# main-uass.net
KiCad netlist of a schematic drawn in EAGLE
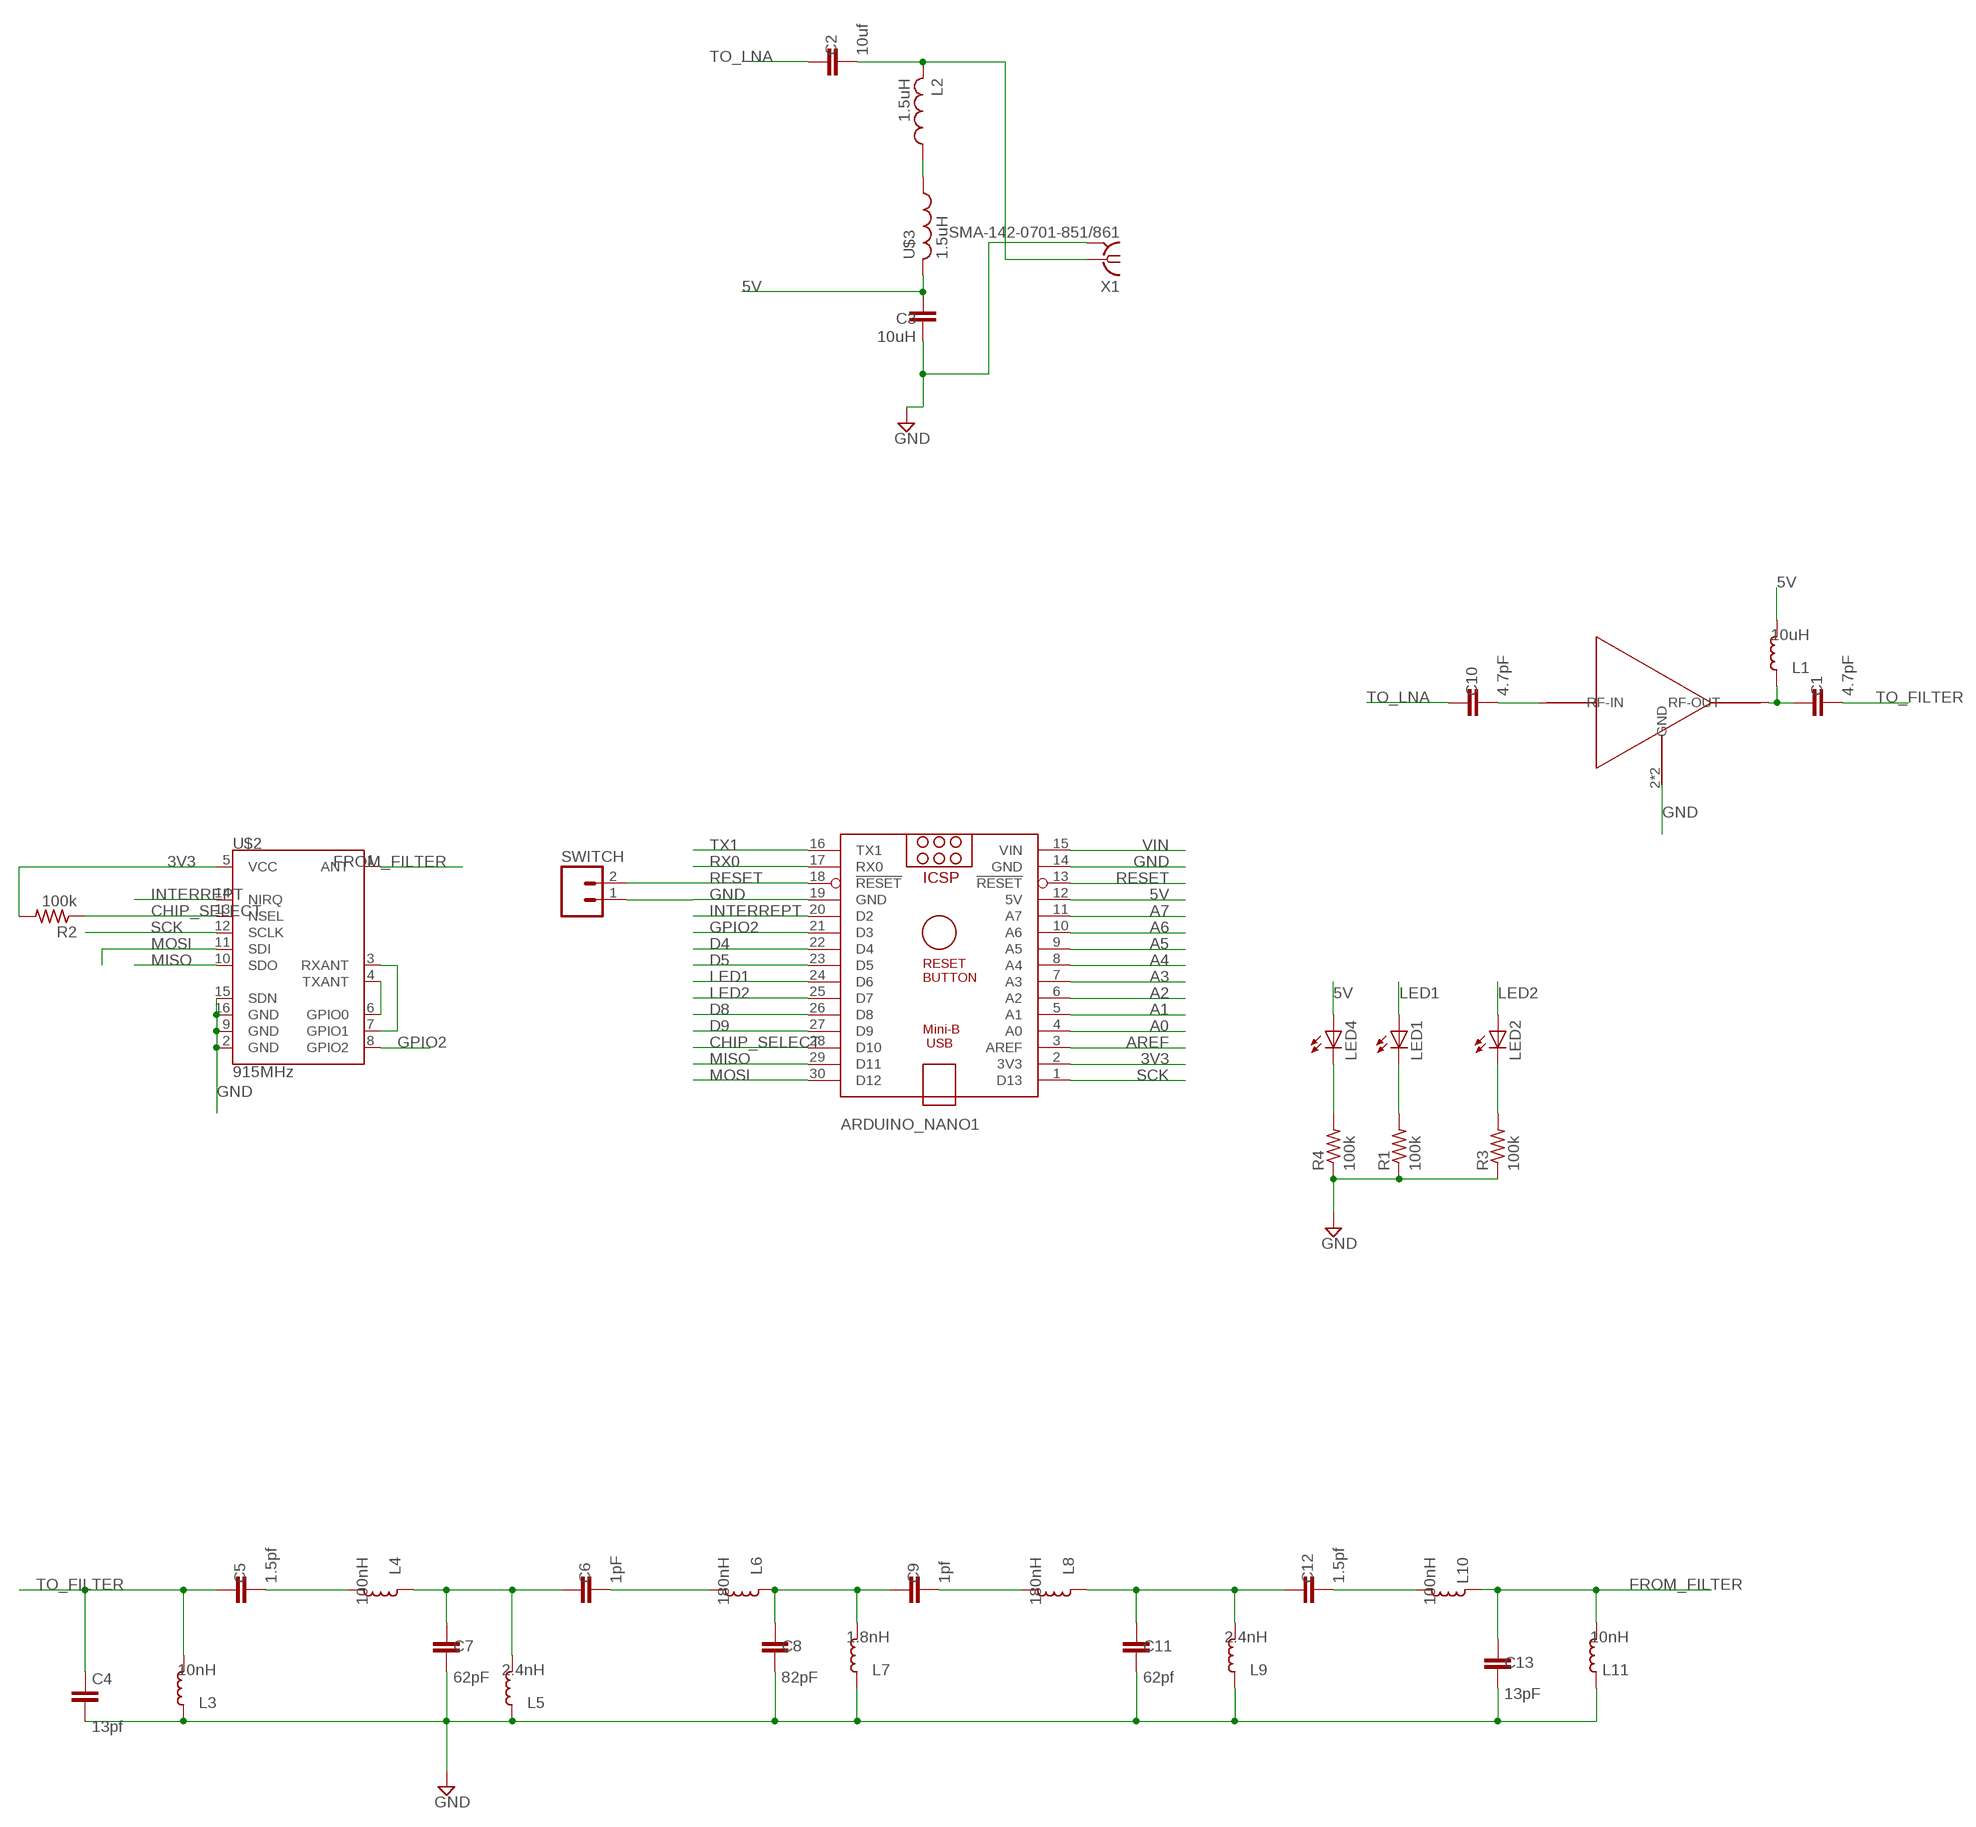
[diagram p0: schematic, sheet 1]

(export (version "E")
  (design (tool "Eeschema 10.0.6"))
  (components
    (comp (ref "ARDUINO_NANO1")
      (value "ARDUINO_NANO")
      (footprint "eagle-import:ARDUINO_NANO")
      (libsource (lib "eagle-import") (part "ARDUINO_NANO"))
    )
    (comp (ref "C1")
      (value "4.7pF")
      (footprint "eagle-import:0603")
      (libsource (lib "eagle-import") (part "10UF-0603-6.3V-20%"))
    )
    (comp (ref "C2")
      (value "10uf")
      (footprint "eagle-import:0603")
      (libsource (lib "eagle-import") (part "10UF-0603-6.3V-20%"))
    )
    (comp (ref "C3")
      (value "10uH")
      (footprint "eagle-import:0603")
      (libsource (lib "eagle-import") (part "10UF-0603-6.3V-20%"))
    )
    (comp (ref "C4")
      (value "13pf")
      (footprint "eagle-import:0603")
      (libsource (lib "eagle-import") (part "10UF-0603-6.3V-20%"))
    )
    (comp (ref "C5")
      (value "1.5pf")
      (footprint "eagle-import:0603")
      (libsource (lib "eagle-import") (part "10UF-0603-6.3V-20%"))
    )
    (comp (ref "C6")
      (value "1pF")
      (footprint "eagle-import:0603")
      (libsource (lib "eagle-import") (part "10UF-0603-6.3V-20%"))
    )
    (comp (ref "C7")
      (value "62pF")
      (footprint "eagle-import:0603")
      (libsource (lib "eagle-import") (part "10UF-0603-6.3V-20%"))
    )
    (comp (ref "C8")
      (value "82pF")
      (footprint "eagle-import:0603")
      (libsource (lib "eagle-import") (part "10UF-0603-6.3V-20%"))
    )
    (comp (ref "C9")
      (value "1pf")
      (footprint "eagle-import:0603")
      (libsource (lib "eagle-import") (part "10UF-0603-6.3V-20%"))
    )
    (comp (ref "C10")
      (value "4.7pF")
      (footprint "eagle-import:0603")
      (libsource (lib "eagle-import") (part "10UF-0603-6.3V-20%"))
    )
    (comp (ref "C11")
      (value "62pf")
      (footprint "eagle-import:0603")
      (libsource (lib "eagle-import") (part "10UF-0603-6.3V-20%"))
    )
    (comp (ref "C12")
      (value "1.5pf")
      (footprint "eagle-import:0603")
      (libsource (lib "eagle-import") (part "10UF-0603-6.3V-20%"))
    )
    (comp (ref "C13")
      (value "13pF")
      (footprint "eagle-import:0603")
      (libsource (lib "eagle-import") (part "10UF-0603-6.3V-20%"))
    )
    (comp (ref "L1")
      (value "10uH")
      (footprint "eagle-import:L0603")
      (libsource (lib "eagle-import") (part "L_0603"))
    )
    (comp (ref "L2")
      (value "1.5uH")
      (footprint "eagle-import:C0504")
      (libsource (lib "eagle-import") (part "L504"))
    )
    (comp (ref "L3")
      (value "10nH")
      (footprint "eagle-import:L0603")
      (libsource (lib "eagle-import") (part "L_0603"))
    )
    (comp (ref "L4")
      (value "100nH")
      (footprint "eagle-import:L0603")
      (libsource (lib "eagle-import") (part "L_0603"))
    )
    (comp (ref "L5")
      (value "2.4nH")
      (footprint "eagle-import:L0603")
      (libsource (lib "eagle-import") (part "L_0603"))
    )
    (comp (ref "L6")
      (value "180nH")
      (footprint "eagle-import:L0603")
      (libsource (lib "eagle-import") (part "L_0603"))
    )
    (comp (ref "L7")
      (value "1.8nH")
      (footprint "eagle-import:L0603")
      (libsource (lib "eagle-import") (part "L_0603"))
    )
    (comp (ref "L8")
      (value "180nH")
      (footprint "eagle-import:L0603")
      (libsource (lib "eagle-import") (part "L_0603"))
    )
    (comp (ref "L9")
      (value "2.4nH")
      (footprint "eagle-import:L0603")
      (libsource (lib "eagle-import") (part "L_0603"))
    )
    (comp (ref "L10")
      (value "100nH")
      (footprint "eagle-import:L0603")
      (libsource (lib "eagle-import") (part "L_0603"))
    )
    (comp (ref "L11")
      (value "10nH")
      (footprint "eagle-import:L0603")
      (libsource (lib "eagle-import") (part "L_0603"))
    )
    (comp (ref "LED1")
      (value "LED5MM")
      (footprint "eagle-import:LED5MM")
      (libsource (lib "eagle-import") (part "LED5MM"))
    )
    (comp (ref "LED2")
      (value "LED5MM")
      (footprint "eagle-import:LED5MM")
      (libsource (lib "eagle-import") (part "LED5MM"))
    )
    (comp (ref "LED4")
      (value "LED5MM")
      (footprint "eagle-import:LED5MM")
      (libsource (lib "eagle-import") (part "LED5MM"))
    )
    (comp (ref "R1")
      (value "100k")
      (footprint "eagle-import:R0603")
      (libsource (lib "eagle-import") (part "R-US_R0603"))
    )
    (comp (ref "R2")
      (value "100k")
      (footprint "eagle-import:R0603")
      (libsource (lib "eagle-import") (part "R-US_R0603"))
    )
    (comp (ref "R3")
      (value "100k")
      (footprint "eagle-import:R0603")
      (libsource (lib "eagle-import") (part "R-US_R0603"))
    )
    (comp (ref "R4")
      (value "100k")
      (footprint "eagle-import:R0603")
      (libsource (lib "eagle-import") (part "R-US_R0603"))
    )
    (comp (ref "SWITCH")
      (value "M02")
      (footprint "eagle-import:02P")
      (libsource (lib "eagle-import") (part "M02"))
    )
    (comp (ref "U$1")
      (value "PSA4-5043+")
      (footprint "eagle-import:PSA4-5043+")
      (fields (field (name "MF") "Mini-Circuits"))
      (libsource (lib "eagle-import") (part "PSA4-5043+"))
    )
    (comp (ref "U$2")
      (value "915MHz")
      (footprint "eagle-import:RFM22-XXX-S2")
      (libsource (lib "eagle-import") (part "RFM22915MHZ"))
    )
    (comp (ref "U$3")
      (value "1.5uH")
      (footprint "eagle-import:C0504")
      (libsource (lib "eagle-import") (part "L504"))
    )
    (comp (ref "X1")
      (value "SMA-142-0701-851/861")
      (footprint "eagle-import:J502-ND-142-0701-851_861")
      (fields (field (name "MF") "JOHNSON COMPONENTS") (field (name "MPN") "142-0701-851"))
      (libsource (lib "eagle-import") (part "SMA-142-0701-851/861"))
    )
  )
  (nets
    (net (code "1") (name "/3V3") (class "Default")
      (node (ref "ARDUINO_NANO1") (pin "2") (pinfunction "3V3_2") (pintype "output"))
      (node (ref "R2") (pin "2") (pinfunction "2_2") (pintype "passive"))
      (node (ref "U$2") (pin "5") (pinfunction "VCC_5") (pintype "bidirectional"))
    )
    (net (code "2") (name "/5V") (class "Default")
      (node (ref "ARDUINO_NANO1") (pin "12") (pinfunction "5V_12") (pintype "power_in"))
      (node (ref "C3") (pin "2") (pinfunction "2_2") (pintype "passive"))
      (node (ref "L1") (pin "1") (pinfunction "1_1") (pintype "passive"))
      (node (ref "LED4") (pin "A") (pinfunction "A_A") (pintype "passive"))
      (node (ref "U$3") (pin "2") (pinfunction "2_2") (pintype "passive"))
    )
    (net (code "3") (name "/A0") (class "Default")
      (node (ref "ARDUINO_NANO1") (pin "4") (pinfunction "A0_4") (pintype "bidirectional"))
    )
    (net (code "4") (name "/A1") (class "Default")
      (node (ref "ARDUINO_NANO1") (pin "5") (pinfunction "A1_5") (pintype "bidirectional"))
    )
    (net (code "5") (name "/A2") (class "Default")
      (node (ref "ARDUINO_NANO1") (pin "6") (pinfunction "A2_6") (pintype "bidirectional"))
    )
    (net (code "6") (name "/A3") (class "Default")
      (node (ref "ARDUINO_NANO1") (pin "7") (pinfunction "A3_7") (pintype "bidirectional"))
    )
    (net (code "7") (name "/A4") (class "Default")
      (node (ref "ARDUINO_NANO1") (pin "8") (pinfunction "A4_8") (pintype "bidirectional"))
    )
    (net (code "8") (name "/A5") (class "Default")
      (node (ref "ARDUINO_NANO1") (pin "9") (pinfunction "A5_9") (pintype "bidirectional"))
    )
    (net (code "9") (name "/A6") (class "Default")
      (node (ref "ARDUINO_NANO1") (pin "10") (pinfunction "A6_10") (pintype "bidirectional"))
    )
    (net (code "10") (name "/A7") (class "Default")
      (node (ref "ARDUINO_NANO1") (pin "11") (pinfunction "A7_11") (pintype "bidirectional"))
    )
    (net (code "11") (name "/AREF") (class "Default")
      (node (ref "ARDUINO_NANO1") (pin "3") (pinfunction "AREF_3") (pintype "input"))
    )
    (net (code "12") (name "/CHIP_SELECT") (class "Default")
      (node (ref "ARDUINO_NANO1") (pin "28") (pinfunction "D10_28") (pintype "bidirectional"))
      (node (ref "R2") (pin "1") (pinfunction "1_1") (pintype "passive"))
      (node (ref "U$2") (pin "13") (pinfunction "NSEL_13") (pintype "input"))
    )
    (net (code "13") (name "/D4") (class "Default")
      (node (ref "ARDUINO_NANO1") (pin "22") (pinfunction "D4_22") (pintype "bidirectional"))
    )
    (net (code "14") (name "/D5") (class "Default")
      (node (ref "ARDUINO_NANO1") (pin "23") (pinfunction "D5_23") (pintype "bidirectional"))
    )
    (net (code "15") (name "/D8") (class "Default")
      (node (ref "ARDUINO_NANO1") (pin "26") (pinfunction "D8_26") (pintype "bidirectional"))
    )
    (net (code "16") (name "/D9") (class "Default")
      (node (ref "ARDUINO_NANO1") (pin "27") (pinfunction "D9_27") (pintype "bidirectional"))
    )
    (net (code "17") (name "/FROM_FILTER") (class "Default")
      (node (ref "C13") (pin "1") (pinfunction "1_1") (pintype "passive"))
      (node (ref "L10") (pin "2") (pinfunction "2_2") (pintype "passive"))
      (node (ref "L11") (pin "1") (pinfunction "1_1") (pintype "passive"))
      (node (ref "U$2") (pin "1") (pinfunction "ANT_1") (pintype "bidirectional"))
    )
    (net (code "18") (name "/GPIO2") (class "Default")
      (node (ref "ARDUINO_NANO1") (pin "21") (pinfunction "D3_21") (pintype "bidirectional"))
      (node (ref "U$2") (pin "8") (pinfunction "GPIO2_8") (pintype "bidirectional"))
    )
    (net (code "19") (name "/INTERREPT") (class "Default")
      (node (ref "ARDUINO_NANO1") (pin "20") (pinfunction "D2_20") (pintype "bidirectional"))
      (node (ref "U$2") (pin "14") (pinfunction "NIRQ_14") (pintype "output"))
    )
    (net (code "20") (name "/LED1") (class "Default")
      (node (ref "ARDUINO_NANO1") (pin "24") (pinfunction "D6_24") (pintype "bidirectional"))
      (node (ref "LED1") (pin "A") (pinfunction "A_A") (pintype "passive"))
    )
    (net (code "21") (name "/LED2") (class "Default")
      (node (ref "ARDUINO_NANO1") (pin "25") (pinfunction "D7_25") (pintype "bidirectional"))
      (node (ref "LED2") (pin "A") (pinfunction "A_A") (pintype "passive"))
    )
    (net (code "22") (name "/MISO") (class "Default")
      (node (ref "ARDUINO_NANO1") (pin "29") (pinfunction "D11_29") (pintype "bidirectional"))
      (node (ref "U$2") (pin "10") (pinfunction "SDO_10") (pintype "output"))
    )
    (net (code "23") (name "/MOSI") (class "Default")
      (node (ref "ARDUINO_NANO1") (pin "30") (pinfunction "D12_30") (pintype "bidirectional"))
      (node (ref "U$2") (pin "11") (pinfunction "SDI_11") (pintype "input"))
    )
    (net (code "24") (name "/RESET") (class "Default")
      (node (ref "ARDUINO_NANO1") (pin "13") (pinfunction "~{RESET}_13") (pintype "input"))
      (node (ref "ARDUINO_NANO1") (pin "18") (pinfunction "~{RESET}_18") (pintype "input"))
      (node (ref "SWITCH") (pin "2") (pinfunction "2_2") (pintype "passive"))
    )
    (net (code "25") (name "/RX0") (class "Default")
      (node (ref "ARDUINO_NANO1") (pin "17") (pinfunction "RX0_17") (pintype "bidirectional"))
    )
    (net (code "26") (name "/SCK") (class "Default")
      (node (ref "ARDUINO_NANO1") (pin "1") (pinfunction "D13_1") (pintype "bidirectional"))
      (node (ref "U$2") (pin "12") (pinfunction "SCLK_12") (pintype "input"))
    )
    (net (code "27") (name "/TO_FILTER") (class "Default")
      (node (ref "C1") (pin "2") (pinfunction "2_2") (pintype "passive"))
      (node (ref "C4") (pin "1") (pinfunction "1_1") (pintype "passive"))
      (node (ref "C5") (pin "1") (pinfunction "1_1") (pintype "passive"))
      (node (ref "L3") (pin "1") (pinfunction "1_1") (pintype "passive"))
    )
    (net (code "28") (name "/TO_LNA") (class "Default")
      (node (ref "C10") (pin "1") (pinfunction "1_1") (pintype "passive"))
      (node (ref "C2") (pin "1") (pinfunction "1_1") (pintype "passive"))
    )
    (net (code "29") (name "/TX1") (class "Default")
      (node (ref "ARDUINO_NANO1") (pin "16") (pinfunction "TX1_16") (pintype "bidirectional"))
    )
    (net (code "30") (name "/VIN") (class "Default")
      (node (ref "ARDUINO_NANO1") (pin "15") (pinfunction "VIN_15") (pintype "power_in"))
    )
    (net (code "31") (name "GND") (class "Default")
      (node (ref "ARDUINO_NANO1") (pin "14") (pinfunction "GND_14") (pintype "power_in"))
      (node (ref "ARDUINO_NANO1") (pin "19") (pinfunction "GND_19") (pintype "power_in"))
      (node (ref "C11") (pin "2") (pinfunction "2_2") (pintype "passive"))
      (node (ref "C13") (pin "2") (pinfunction "2_2") (pintype "passive"))
      (node (ref "C3") (pin "1") (pinfunction "1_1") (pintype "passive"))
      (node (ref "C4") (pin "2") (pinfunction "2_2") (pintype "passive"))
      (node (ref "C7") (pin "2") (pinfunction "2_2") (pintype "passive"))
      (node (ref "C8") (pin "2") (pinfunction "2_2") (pintype "passive"))
      (node (ref "L11") (pin "2") (pinfunction "2_2") (pintype "passive"))
      (node (ref "L3") (pin "2") (pinfunction "2_2") (pintype "passive"))
      (node (ref "L5") (pin "2") (pinfunction "2_2") (pintype "passive"))
      (node (ref "L7") (pin "2") (pinfunction "2_2") (pintype "passive"))
      (node (ref "L9") (pin "2") (pinfunction "2_2") (pintype "passive"))
      (node (ref "R1") (pin "1") (pinfunction "1_1") (pintype "passive"))
      (node (ref "R3") (pin "1") (pinfunction "1_1") (pintype "passive"))
      (node (ref "R4") (pin "1") (pinfunction "1_1") (pintype "passive"))
      (node (ref "SWITCH") (pin "1") (pinfunction "1_1") (pintype "passive"))
      (node (ref "U$1") (pin "2") (pinfunction "GND_2") (pintype "bidirectional"))
      (node (ref "U$1") (pin "4") (pinfunction "GND_4") (pintype "bidirectional"))
      (node (ref "U$2") (pin "15") (pinfunction "SDN_15") (pintype "input"))
      (node (ref "U$2") (pin "16") (pinfunction "GND_16") (pintype "power_in"))
      (node (ref "U$2") (pin "2") (pinfunction "GND_2") (pintype "power_in"))
      (node (ref "U$2") (pin "9") (pinfunction "GND_9") (pintype "power_in"))
      (node (ref "X1") (pin "G@1") (pinfunction "2_G@1") (pintype "passive"))
      (node (ref "X1") (pin "G@2") (pinfunction "2_G@2") (pintype "passive"))
      (node (ref "X1") (pin "G@3") (pinfunction "2_G@3") (pintype "passive"))
      (node (ref "X1") (pin "G@4") (pinfunction "2_G@4") (pintype "passive"))
    )
    (net (code "32") (name "Net-(C2-Pad2)") (class "Default")
      (node (ref "C2") (pin "2") (pinfunction "2_2") (pintype "passive"))
      (node (ref "L2") (pin "2") (pinfunction "2_2") (pintype "passive"))
      (node (ref "X1") (pin "1") (pinfunction "1_1") (pintype "passive"))
    )
    (net (code "33") (name "Net-(C5-Pad2)") (class "Default")
      (node (ref "C5") (pin "2") (pinfunction "2_2") (pintype "passive"))
      (node (ref "L4") (pin "1") (pinfunction "1_1") (pintype "passive"))
    )
    (net (code "34") (name "Net-(C6-Pad1)") (class "Default")
      (node (ref "C6") (pin "1") (pinfunction "1_1") (pintype "passive"))
      (node (ref "C7") (pin "1") (pinfunction "1_1") (pintype "passive"))
      (node (ref "L4") (pin "2") (pinfunction "2_2") (pintype "passive"))
      (node (ref "L5") (pin "1") (pinfunction "1_1") (pintype "passive"))
    )
    (net (code "35") (name "Net-(C6-Pad2)") (class "Default")
      (node (ref "C6") (pin "2") (pinfunction "2_2") (pintype "passive"))
      (node (ref "L6") (pin "1") (pinfunction "1_1") (pintype "passive"))
    )
    (net (code "36") (name "Net-(C8-Pad1)") (class "Default")
      (node (ref "C8") (pin "1") (pinfunction "1_1") (pintype "passive"))
      (node (ref "C9") (pin "1") (pinfunction "1_1") (pintype "passive"))
      (node (ref "L6") (pin "2") (pinfunction "2_2") (pintype "passive"))
      (node (ref "L7") (pin "1") (pinfunction "1_1") (pintype "passive"))
    )
    (net (code "37") (name "Net-(C9-Pad2)") (class "Default")
      (node (ref "C9") (pin "2") (pinfunction "2_2") (pintype "passive"))
      (node (ref "L8") (pin "1") (pinfunction "1_1") (pintype "passive"))
    )
    (net (code "38") (name "Net-(C11-Pad1)") (class "Default")
      (node (ref "C11") (pin "1") (pinfunction "1_1") (pintype "passive"))
      (node (ref "C12") (pin "1") (pinfunction "1_1") (pintype "passive"))
      (node (ref "L8") (pin "2") (pinfunction "2_2") (pintype "passive"))
      (node (ref "L9") (pin "1") (pinfunction "1_1") (pintype "passive"))
    )
    (net (code "39") (name "Net-(C12-Pad2)") (class "Default")
      (node (ref "C12") (pin "2") (pinfunction "2_2") (pintype "passive"))
      (node (ref "L10") (pin "1") (pinfunction "1_1") (pintype "passive"))
    )
    (net (code "40") (name "Net-(L2-Pad1)") (class "Default")
      (node (ref "L2") (pin "1") (pinfunction "1_1") (pintype "passive"))
      (node (ref "U$3") (pin "1") (pinfunction "1_1") (pintype "passive"))
    )
    (net (code "41") (name "Net-(LED1-C)") (class "Default")
      (node (ref "LED1") (pin "K") (pinfunction "C_K") (pintype "passive"))
      (node (ref "R1") (pin "2") (pinfunction "2_2") (pintype "passive"))
    )
    (net (code "42") (name "Net-(LED2-C)") (class "Default")
      (node (ref "LED2") (pin "K") (pinfunction "C_K") (pintype "passive"))
      (node (ref "R3") (pin "2") (pinfunction "2_2") (pintype "passive"))
    )
    (net (code "43") (name "Net-(LED4-C)") (class "Default")
      (node (ref "LED4") (pin "K") (pinfunction "C_K") (pintype "passive"))
      (node (ref "R4") (pin "2") (pinfunction "2_2") (pintype "passive"))
    )
    (net (code "44") (name "Net-(U$1-RF-IN)") (class "Default")
      (node (ref "C10") (pin "2") (pinfunction "2_2") (pintype "passive"))
      (node (ref "U$1") (pin "3") (pinfunction "RF-IN_3") (pintype "bidirectional"))
    )
    (net (code "45") (name "Net-(U$1-RF-OUT)") (class "Default")
      (node (ref "C1") (pin "1") (pinfunction "1_1") (pintype "passive"))
      (node (ref "L1") (pin "2") (pinfunction "2_2") (pintype "passive"))
      (node (ref "U$1") (pin "1") (pinfunction "RF-OUT_1") (pintype "bidirectional"))
    )
    (net (code "46") (name "Net-(U$2-GPIO0)") (class "Default")
      (node (ref "U$2") (pin "4") (pinfunction "TXANT_4") (pintype "input"))
      (node (ref "U$2") (pin "6") (pinfunction "GPIO0_6") (pintype "bidirectional"))
    )
    (net (code "47") (name "Net-(U$2-GPIO1)") (class "Default")
      (node (ref "U$2") (pin "3") (pinfunction "RXANT_3") (pintype "input"))
      (node (ref "U$2") (pin "7") (pinfunction "GPIO1_7") (pintype "bidirectional"))
    )
  )
)
